# oscillator_tolerance.net
KiCad netlist of a schematic drawn in Altium Designer
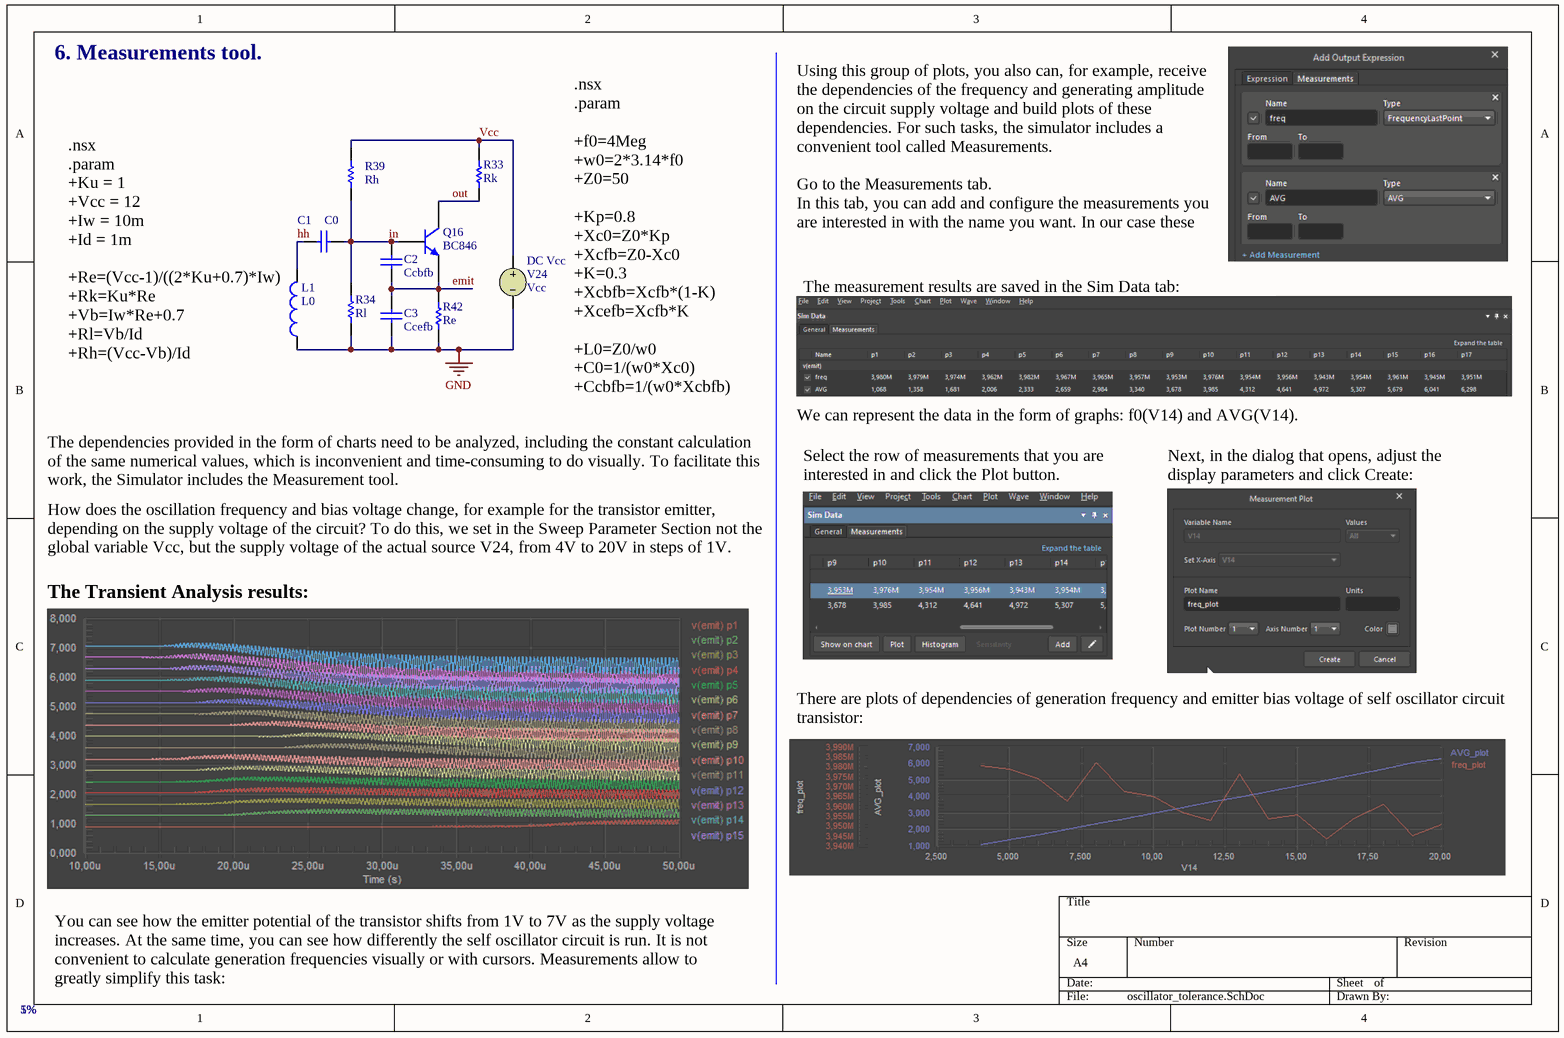
[diagram p0: oscillator_tolerance.SchDoc]

(export (version "E")
  (design (tool "Eeschema 10.0.6"))
  (components
    (comp (ref "C1")
      (value "C0")
      (description "Capacitor")
      (libsource (lib "Simulation Generic Components") (part "Capacitor"))
    )
    (comp (ref "C2")
      (value "Ccbfb")
      (description "Capacitor")
      (libsource (lib "Simulation Generic Components") (part "Capacitor"))
    )
    (comp (ref "C3")
      (value "Ccefb")
      (description "Capacitor")
      (libsource (lib "Simulation Generic Components") (part "Capacitor"))
    )
    (comp (ref "L1")
      (value "L0")
      (description "Inductor")
      (libsource (lib "Simulation Generic Components") (part "Inductor"))
    )
    (comp (ref "Q16")
      (value "BC846")
      (footprint "TO-92A")
      (description "NPN General Purpose Amplifier")
      (fields (field (name "PUBLISHER") "Altium Limited"))
      (libsource (lib "Miscellaneous Devices") (part "2N3904"))
    )
    (comp (ref "R33")
      (value "Rk")
      (description "Resistor")
      (fields (field (name "TOLERANCE") "5%"))
      (libsource (lib "Simulation Generic Components") (part "Resistor"))
    )
    (comp (ref "R34")
      (value "Rl")
      (description "Resistor")
      (fields (field (name "TOLERANCE") "5%"))
      (libsource (lib "Simulation Generic Components") (part "Resistor"))
    )
    (comp (ref "R39")
      (value "Rh")
      (description "Resistor")
      (fields (field (name "TOLERANCE") "5%"))
      (libsource (lib "Simulation Generic Components") (part "Resistor"))
    )
    (comp (ref "R42")
      (value "Re")
      (description "Resistor")
      (fields (field (name "TOLERANCE") "1%"))
      (libsource (lib "Simulation Generic Components") (part "Resistor"))
    )
    (comp (ref "V24")
      (value "DC Vcc")
      (description "Voltage Source")
      (fields (field (name "ALTIUM_VALUE") "Vcc") (field (name "PUBLISHER") "Altium Limited"))
      (libsource (lib "Simulation Generic Components") (part "VSRC"))
    )
  )
  (nets
    (net (code "1") (name "/Vcc") (class "Default")
      (node (ref "R33") (pin "2") (pinfunction "2_2") (pintype "passive"))
      (node (ref "R39") (pin "2") (pinfunction "2_2") (pintype "passive"))
      (node (ref "V24") (pin "1") (pinfunction "1_1") (pintype "passive"))
    )
    (net (code "2") (name "/emit") (class "Default")
      (node (ref "C2") (pin "1") (pinfunction "1_1") (pintype "passive"))
      (node (ref "C3") (pin "2") (pinfunction "2_2") (pintype "passive"))
      (node (ref "Q16") (pin "1") (pinfunction "E_1") (pintype "passive"))
      (node (ref "R42") (pin "2") (pinfunction "2_2") (pintype "passive"))
    )
    (net (code "3") (name "/hh") (class "Default")
      (node (ref "C1") (pin "1") (pinfunction "1_1") (pintype "passive"))
      (node (ref "L1") (pin "2") (pinfunction "2_2") (pintype "passive"))
    )
    (net (code "4") (name "/in") (class "Default")
      (node (ref "C1") (pin "2") (pinfunction "2_2") (pintype "passive"))
      (node (ref "C2") (pin "2") (pinfunction "2_2") (pintype "passive"))
      (node (ref "Q16") (pin "2") (pinfunction "B_2") (pintype "passive"))
      (node (ref "R34") (pin "1") (pinfunction "1_1") (pintype "passive"))
      (node (ref "R39") (pin "1") (pinfunction "1_1") (pintype "passive"))
    )
    (net (code "5") (name "/out") (class "Default")
      (node (ref "Q16") (pin "3") (pinfunction "C_3") (pintype "passive"))
      (node (ref "R33") (pin "1") (pinfunction "1_1") (pintype "passive"))
    )
    (net (code "6") (name "GND") (class "Default")
      (node (ref "C3") (pin "1") (pinfunction "1_1") (pintype "passive"))
      (node (ref "L1") (pin "1") (pinfunction "1_1") (pintype "passive"))
      (node (ref "R34") (pin "2") (pinfunction "2_2") (pintype "passive"))
      (node (ref "R42") (pin "1") (pinfunction "1_1") (pintype "passive"))
      (node (ref "V24") (pin "2") (pinfunction "2_2") (pintype "passive"))
    )
  )
)
